# Vent_Base.net
KiCad netlist of a schematic drawn in EAGLE
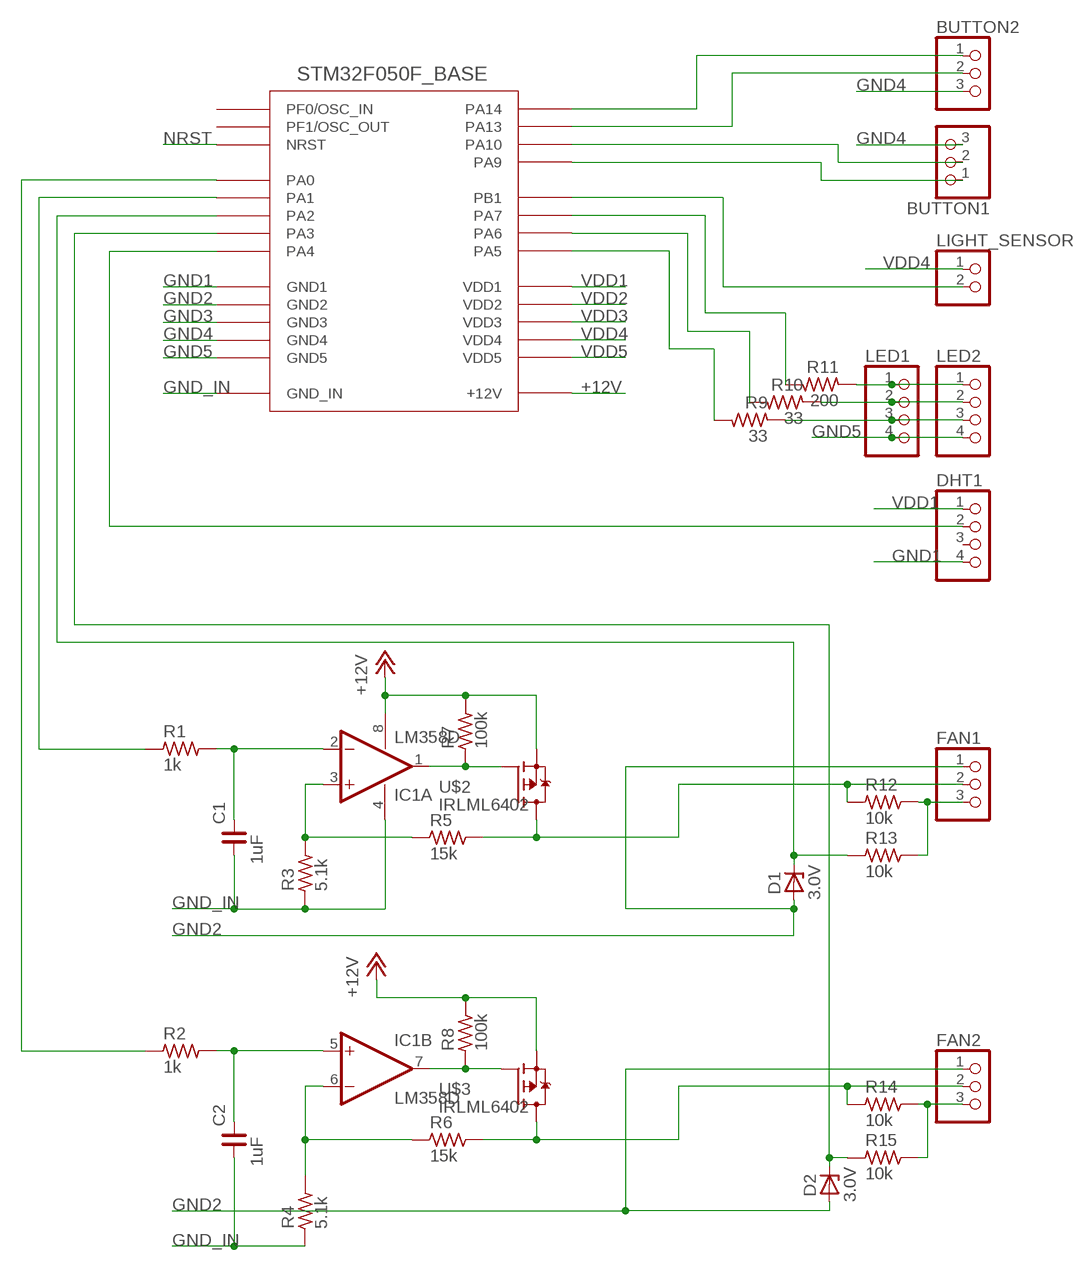
[diagram p0: schematic, sheet 1]

(export (version "E")
  (design (tool "Eeschema 10.0.6"))
  (components
    (comp (ref "BUTTON1")
      (value "PINHD-1X03_2.54-S")
      (footprint "eagle-import:1X03-S")
      (libsource (lib "eagle-import") (part "PINHD-1X03_2.54-S"))
    )
    (comp (ref "BUTTON2")
      (value "PINHD-1X03_2.54-S")
      (footprint "eagle-import:1X03-S")
      (libsource (lib "eagle-import") (part "PINHD-1X03_2.54-S"))
    )
    (comp (ref "C1")
      (value "1uF")
      (footprint "eagle-import:C0805")
      (libsource (lib "eagle-import") (part "C_0805"))
    )
    (comp (ref "C2")
      (value "1uF")
      (footprint "eagle-import:C0805")
      (libsource (lib "eagle-import") (part "C_0805"))
    )
    (comp (ref "D1")
      (value "ZENER-DIODESOT23")
      (footprint "eagle-import:SOT23")
      (fields (field (name "BZX84C3V0") "3.0V"))
      (libsource (lib "eagle-import") (part "ZENER-DIODESOT23"))
    )
    (comp (ref "D2")
      (value "ZENER-DIODESOT23")
      (footprint "eagle-import:SOT23")
      (fields (field (name "BZX84C3V0") "3.0V"))
      (libsource (lib "eagle-import") (part "ZENER-DIODESOT23"))
    )
    (comp (ref "DHT1")
      (value "PINHD-1X04_2.54-S")
      (footprint "eagle-import:1X04-S")
      (libsource (lib "eagle-import") (part "PINHD-1X04_2.54-S"))
    )
    (comp (ref "FAN1")
      (value "PINHD-1X03_2.54-S")
      (footprint "eagle-import:1X03-S")
      (libsource (lib "eagle-import") (part "PINHD-1X03_2.54-S"))
    )
    (comp (ref "FAN2")
      (value "PINHD-1X03_2.54-S")
      (footprint "eagle-import:1X03-S")
      (libsource (lib "eagle-import") (part "PINHD-1X03_2.54-S"))
    )
    (comp (ref "IC1")
      (value "LM358D")
      (footprint "eagle-import:SO08")
      (libsource (lib "eagle-import") (part "LM358D"))
    )
    (comp (ref "LED1")
      (value "PINHD-1X04_2.54-S")
      (footprint "eagle-import:1X04-S")
      (libsource (lib "eagle-import") (part "PINHD-1X04_2.54-S"))
    )
    (comp (ref "LED2")
      (value "PINHD-1X04_2.54-S")
      (footprint "eagle-import:1X04-S")
      (libsource (lib "eagle-import") (part "PINHD-1X04_2.54-S"))
    )
    (comp (ref "LIGHT_SENSOR")
      (value "PINHD-1X02_2.54-S")
      (footprint "eagle-import:1X02-S")
      (libsource (lib "eagle-import") (part "PINHD-1X02_2.54-S"))
    )
    (comp (ref "R1")
      (value "1k")
      (footprint "eagle-import:R1206")
      (libsource (lib "eagle-import") (part "R_1206"))
    )
    (comp (ref "R2")
      (value "1k")
      (footprint "eagle-import:R1206")
      (libsource (lib "eagle-import") (part "R_1206"))
    )
    (comp (ref "R3")
      (value "5.1k")
      (footprint "eagle-import:R1206")
      (libsource (lib "eagle-import") (part "R_1206"))
    )
    (comp (ref "R4")
      (value "5.1k")
      (footprint "eagle-import:R1206")
      (libsource (lib "eagle-import") (part "R_1206"))
    )
    (comp (ref "R5")
      (value "15k")
      (footprint "eagle-import:R1206")
      (libsource (lib "eagle-import") (part "R_1206"))
    )
    (comp (ref "R6")
      (value "15k")
      (footprint "eagle-import:R1206")
      (libsource (lib "eagle-import") (part "R_1206"))
    )
    (comp (ref "R7")
      (value "100k")
      (footprint "eagle-import:R1206")
      (libsource (lib "eagle-import") (part "R_1206"))
    )
    (comp (ref "R8")
      (value "100k")
      (footprint "eagle-import:R1206")
      (libsource (lib "eagle-import") (part "R_1206"))
    )
    (comp (ref "R9")
      (value "33")
      (footprint "eagle-import:R0805")
      (libsource (lib "eagle-import") (part "R_0805"))
    )
    (comp (ref "R10")
      (value "33")
      (footprint "eagle-import:R0805")
      (libsource (lib "eagle-import") (part "R_0805"))
    )
    (comp (ref "R11")
      (value "200")
      (footprint "eagle-import:R0805")
      (libsource (lib "eagle-import") (part "R_0805"))
    )
    (comp (ref "R12")
      (value "10k")
      (footprint "eagle-import:R1206")
      (libsource (lib "eagle-import") (part "R_1206"))
    )
    (comp (ref "R13")
      (value "10k")
      (footprint "eagle-import:R1206")
      (libsource (lib "eagle-import") (part "R_1206"))
    )
    (comp (ref "R14")
      (value "10k")
      (footprint "eagle-import:R1206")
      (libsource (lib "eagle-import") (part "R_1206"))
    )
    (comp (ref "R15")
      (value "10k")
      (footprint "eagle-import:R1206")
      (libsource (lib "eagle-import") (part "R_1206"))
    )
    (comp (ref "U$1")
      (value "STM32F050F_BASE_MOD")
      (footprint "eagle-import:STM32_BASE_MOD")
      (libsource (lib "eagle-import") (part "STM32F050F_BASE_MOD"))
    )
    (comp (ref "U$2")
      (value "IRLML6402")
      (footprint "eagle-import:SOT23")
      (libsource (lib "eagle-import") (part "IRLML6402"))
    )
    (comp (ref "U$3")
      (value "IRLML6402")
      (footprint "eagle-import:SOT23")
      (libsource (lib "eagle-import") (part "IRLML6402"))
    )
  )
  (nets
    (net (code "1") (name "+12V") (class "Default")
      (node (ref "IC1") (pin "8") (pinfunction "V+_8") (pintype "power_in"))
      (node (ref "R7") (pin "2") (pinfunction "2_2") (pintype "passive"))
      (node (ref "R8") (pin "2") (pinfunction "2_2") (pintype "passive"))
      (node (ref "U$1") (pin "+12V") (pinfunction "+12V_+12V") (pintype "passive"))
      (node (ref "U$2") (pin "2") (pinfunction "S_2") (pintype "passive"))
      (node (ref "U$3") (pin "2") (pinfunction "S_2") (pintype "passive"))
    )
    (net (code "2") (name "/GND1") (class "Default")
      (node (ref "DHT1") (pin "4") (pinfunction "4_4") (pintype "passive"))
      (node (ref "U$1") (pin "GND1") (pinfunction "GND1_GND1") (pintype "passive"))
    )
    (net (code "3") (name "/GND2") (class "Default")
      (node (ref "D1") (pin "1") (pinfunction "A_1") (pintype "passive"))
      (node (ref "D2") (pin "1") (pinfunction "A_1") (pintype "passive"))
      (node (ref "FAN1") (pin "1") (pinfunction "1_1") (pintype "passive"))
      (node (ref "FAN2") (pin "1") (pinfunction "1_1") (pintype "passive"))
      (node (ref "U$1") (pin "GND2") (pinfunction "GND2_GND2") (pintype "passive"))
    )
    (net (code "4") (name "/GND3") (class "Default")
      (node (ref "U$1") (pin "GND3") (pinfunction "GND3_GND3") (pintype "passive"))
    )
    (net (code "5") (name "/GND4") (class "Default")
      (node (ref "BUTTON1") (pin "3") (pinfunction "3_3") (pintype "passive"))
      (node (ref "BUTTON2") (pin "3") (pinfunction "3_3") (pintype "passive"))
      (node (ref "U$1") (pin "GND4") (pinfunction "GND4_GND4") (pintype "passive"))
    )
    (net (code "6") (name "/GND5") (class "Default")
      (node (ref "LED1") (pin "4") (pinfunction "4_4") (pintype "passive"))
      (node (ref "LED2") (pin "4") (pinfunction "4_4") (pintype "passive"))
      (node (ref "U$1") (pin "GND5") (pinfunction "GND5_GND5") (pintype "passive"))
    )
    (net (code "7") (name "/GND_IN") (class "Default")
      (node (ref "C1") (pin "1") (pinfunction "1_1") (pintype "passive"))
      (node (ref "C2") (pin "1") (pinfunction "1_1") (pintype "passive"))
      (node (ref "IC1") (pin "4") (pinfunction "V-_4") (pintype "power_in"))
      (node (ref "R3") (pin "1") (pinfunction "1_1") (pintype "passive"))
      (node (ref "R4") (pin "1") (pinfunction "1_1") (pintype "passive"))
      (node (ref "U$1") (pin "GND_IN") (pinfunction "GND_IN_GND_IN") (pintype "passive"))
    )
    (net (code "8") (name "/NRST") (class "Default")
      (node (ref "U$1") (pin "NRST") (pinfunction "NRST_NRST") (pintype "passive"))
    )
    (net (code "9") (name "/VDD1") (class "Default")
      (node (ref "DHT1") (pin "1") (pinfunction "1_1") (pintype "passive"))
      (node (ref "U$1") (pin "VDD1") (pinfunction "VDD1_VDD1") (pintype "passive"))
    )
    (net (code "10") (name "/VDD2") (class "Default")
      (node (ref "U$1") (pin "VDD2") (pinfunction "VDD2_VDD2") (pintype "passive"))
    )
    (net (code "11") (name "/VDD3") (class "Default")
      (node (ref "U$1") (pin "VDD3") (pinfunction "VDD3_VDD3") (pintype "passive"))
    )
    (net (code "12") (name "/VDD4") (class "Default")
      (node (ref "LIGHT_SENSOR") (pin "1") (pinfunction "1_1") (pintype "passive"))
      (node (ref "U$1") (pin "VDD4") (pinfunction "VDD4_VDD4") (pintype "passive"))
    )
    (net (code "13") (name "/VDD5") (class "Default")
      (node (ref "U$1") (pin "VDD5") (pinfunction "VDD5_VDD5") (pintype "passive"))
    )
    (net (code "14") (name "Net-(BUTTON1-Pad1)") (class "Default")
      (node (ref "BUTTON1") (pin "1") (pinfunction "1_1") (pintype "passive"))
      (node (ref "U$1") (pin "PA9") (pinfunction "PA9_PA9") (pintype "passive"))
    )
    (net (code "15") (name "Net-(BUTTON1-Pad2)") (class "Default")
      (node (ref "BUTTON1") (pin "2") (pinfunction "2_2") (pintype "passive"))
      (node (ref "U$1") (pin "PA10") (pinfunction "PA10_PA10") (pintype "passive"))
    )
    (net (code "16") (name "Net-(BUTTON2-Pad1)") (class "Default")
      (node (ref "BUTTON2") (pin "1") (pinfunction "1_1") (pintype "passive"))
      (node (ref "U$1") (pin "PA14") (pinfunction "PA14_PA14") (pintype "passive"))
    )
    (net (code "17") (name "Net-(BUTTON2-Pad2)") (class "Default")
      (node (ref "BUTTON2") (pin "2") (pinfunction "2_2") (pintype "passive"))
      (node (ref "U$1") (pin "PA13") (pinfunction "PA13_PA13") (pintype "passive"))
    )
    (net (code "18") (name "Net-(D1-C)") (class "Default")
      (node (ref "D1") (pin "3") (pinfunction "C_3") (pintype "passive"))
      (node (ref "R13") (pin "1") (pinfunction "1_1") (pintype "passive"))
      (node (ref "U$1") (pin "PA2") (pinfunction "PA2_PA2") (pintype "passive"))
    )
    (net (code "19") (name "Net-(D2-C)") (class "Default")
      (node (ref "D2") (pin "3") (pinfunction "C_3") (pintype "passive"))
      (node (ref "R15") (pin "1") (pinfunction "1_1") (pintype "passive"))
      (node (ref "U$1") (pin "PA3") (pinfunction "PA3_PA3") (pintype "passive"))
    )
    (net (code "20") (name "Net-(DHT1-Pad2)") (class "Default")
      (node (ref "DHT1") (pin "2") (pinfunction "2_2") (pintype "passive"))
      (node (ref "U$1") (pin "PA4") (pinfunction "PA4_PA4") (pintype "passive"))
    )
    (net (code "21") (name "Net-(FAN1-Pad3)") (class "Default")
      (node (ref "FAN1") (pin "3") (pinfunction "3_3") (pintype "passive"))
      (node (ref "R12") (pin "2") (pinfunction "2_2") (pintype "passive"))
      (node (ref "R13") (pin "2") (pinfunction "2_2") (pintype "passive"))
    )
    (net (code "22") (name "Net-(FAN2-Pad3)") (class "Default")
      (node (ref "FAN2") (pin "3") (pinfunction "3_3") (pintype "passive"))
      (node (ref "R14") (pin "2") (pinfunction "2_2") (pintype "passive"))
      (node (ref "R15") (pin "2") (pinfunction "2_2") (pintype "passive"))
    )
    (net (code "23") (name "Net-(IC1A-+IN)") (class "Default")
      (node (ref "IC1") (pin "3") (pinfunction "+IN_3") (pintype "input"))
      (node (ref "R3") (pin "2") (pinfunction "2_2") (pintype "passive"))
      (node (ref "R5") (pin "1") (pinfunction "1_1") (pintype "passive"))
    )
    (net (code "24") (name "Net-(IC1A--IN)") (class "Default")
      (node (ref "C1") (pin "2") (pinfunction "2_2") (pintype "passive"))
      (node (ref "IC1") (pin "2") (pinfunction "-IN_2") (pintype "input"))
      (node (ref "R1") (pin "2") (pinfunction "2_2") (pintype "passive"))
    )
    (net (code "25") (name "Net-(IC1A-OUT)") (class "Default")
      (node (ref "IC1") (pin "1") (pinfunction "OUT_1") (pintype "output"))
      (node (ref "R7") (pin "1") (pinfunction "1_1") (pintype "passive"))
      (node (ref "U$2") (pin "1") (pinfunction "G_1") (pintype "passive"))
    )
    (net (code "26") (name "Net-(IC1B-+IN)") (class "Default")
      (node (ref "C2") (pin "2") (pinfunction "2_2") (pintype "passive"))
      (node (ref "IC1") (pin "5") (pinfunction "+IN_5") (pintype "input"))
      (node (ref "R2") (pin "2") (pinfunction "2_2") (pintype "passive"))
    )
    (net (code "27") (name "Net-(IC1B--IN)") (class "Default")
      (node (ref "IC1") (pin "6") (pinfunction "-IN_6") (pintype "input"))
      (node (ref "R4") (pin "2") (pinfunction "2_2") (pintype "passive"))
      (node (ref "R6") (pin "1") (pinfunction "1_1") (pintype "passive"))
    )
    (net (code "28") (name "Net-(IC1B-OUT)") (class "Default")
      (node (ref "IC1") (pin "7") (pinfunction "OUT_7") (pintype "output"))
      (node (ref "R8") (pin "1") (pinfunction "1_1") (pintype "passive"))
      (node (ref "U$3") (pin "1") (pinfunction "G_1") (pintype "passive"))
    )
    (net (code "29") (name "Net-(LED1-Pad1)") (class "Default")
      (node (ref "LED1") (pin "1") (pinfunction "1_1") (pintype "passive"))
      (node (ref "LED2") (pin "1") (pinfunction "1_1") (pintype "passive"))
      (node (ref "R11") (pin "1") (pinfunction "1_1") (pintype "passive"))
    )
    (net (code "30") (name "Net-(LED1-Pad2)") (class "Default")
      (node (ref "LED1") (pin "2") (pinfunction "2_2") (pintype "passive"))
      (node (ref "LED2") (pin "2") (pinfunction "2_2") (pintype "passive"))
      (node (ref "R10") (pin "1") (pinfunction "1_1") (pintype "passive"))
    )
    (net (code "31") (name "Net-(LED1-Pad3)") (class "Default")
      (node (ref "LED1") (pin "3") (pinfunction "3_3") (pintype "passive"))
      (node (ref "LED2") (pin "3") (pinfunction "3_3") (pintype "passive"))
      (node (ref "R9") (pin "1") (pinfunction "1_1") (pintype "passive"))
    )
    (net (code "32") (name "Net-(LIGHT_SENSOR-Pad2)") (class "Default")
      (node (ref "LIGHT_SENSOR") (pin "2") (pinfunction "2_2") (pintype "passive"))
      (node (ref "U$1") (pin "PB1") (pinfunction "PB1_PB1") (pintype "passive"))
    )
    (net (code "33") (name "Net-(R1-Pad1)") (class "Default")
      (node (ref "R1") (pin "1") (pinfunction "1_1") (pintype "passive"))
      (node (ref "U$1") (pin "PA1") (pinfunction "PA1_PA1") (pintype "passive"))
    )
    (net (code "34") (name "Net-(R2-Pad1)") (class "Default")
      (node (ref "R2") (pin "1") (pinfunction "1_1") (pintype "passive"))
      (node (ref "U$1") (pin "PA0") (pinfunction "PA0_PA0") (pintype "passive"))
    )
    (net (code "35") (name "Net-(R9-Pad2)") (class "Default")
      (node (ref "R9") (pin "2") (pinfunction "2_2") (pintype "passive"))
      (node (ref "U$1") (pin "PA5") (pinfunction "PA5_PA5") (pintype "passive"))
    )
    (net (code "36") (name "Net-(R10-Pad2)") (class "Default")
      (node (ref "R10") (pin "2") (pinfunction "2_2") (pintype "passive"))
      (node (ref "U$1") (pin "PA6") (pinfunction "PA6_PA6") (pintype "passive"))
    )
    (net (code "37") (name "Net-(R11-Pad2)") (class "Default")
      (node (ref "R11") (pin "2") (pinfunction "2_2") (pintype "passive"))
      (node (ref "U$1") (pin "PA7") (pinfunction "PA7_PA7") (pintype "passive"))
    )
    (net (code "38") (name "Net-(U$2-D)") (class "Default")
      (node (ref "FAN1") (pin "2") (pinfunction "2_2") (pintype "passive"))
      (node (ref "R12") (pin "1") (pinfunction "1_1") (pintype "passive"))
      (node (ref "R5") (pin "2") (pinfunction "2_2") (pintype "passive"))
      (node (ref "U$2") (pin "3") (pinfunction "D_3") (pintype "passive"))
    )
    (net (code "39") (name "Net-(U$3-D)") (class "Default")
      (node (ref "FAN2") (pin "2") (pinfunction "2_2") (pintype "passive"))
      (node (ref "R14") (pin "1") (pinfunction "1_1") (pintype "passive"))
      (node (ref "R6") (pin "2") (pinfunction "2_2") (pintype "passive"))
      (node (ref "U$3") (pin "3") (pinfunction "D_3") (pintype "passive"))
    )
    (net (code "40") (name "unconnected-(DHT1-Pad3)") (class "Default")
      (node (ref "DHT1") (pin "3") (pinfunction "3_3") (pintype "passive"))
    )
    (net (code "41") (name "unconnected-(U$1-PF0{slash}OSC_IN-PadPF0)") (class "Default")
      (node (ref "U$1") (pin "PF0") (pinfunction "PF0/OSC_IN_PF0") (pintype "passive"))
    )
    (net (code "42") (name "unconnected-(U$1-PF1{slash}OSC_OUT-PadPF1)") (class "Default")
      (node (ref "U$1") (pin "PF1") (pinfunction "PF1/OSC_OUT_PF1") (pintype "passive"))
    )
  )
)
